# 20x20_adapter_v2.net
KiCad netlist of a schematic drawn in EAGLE
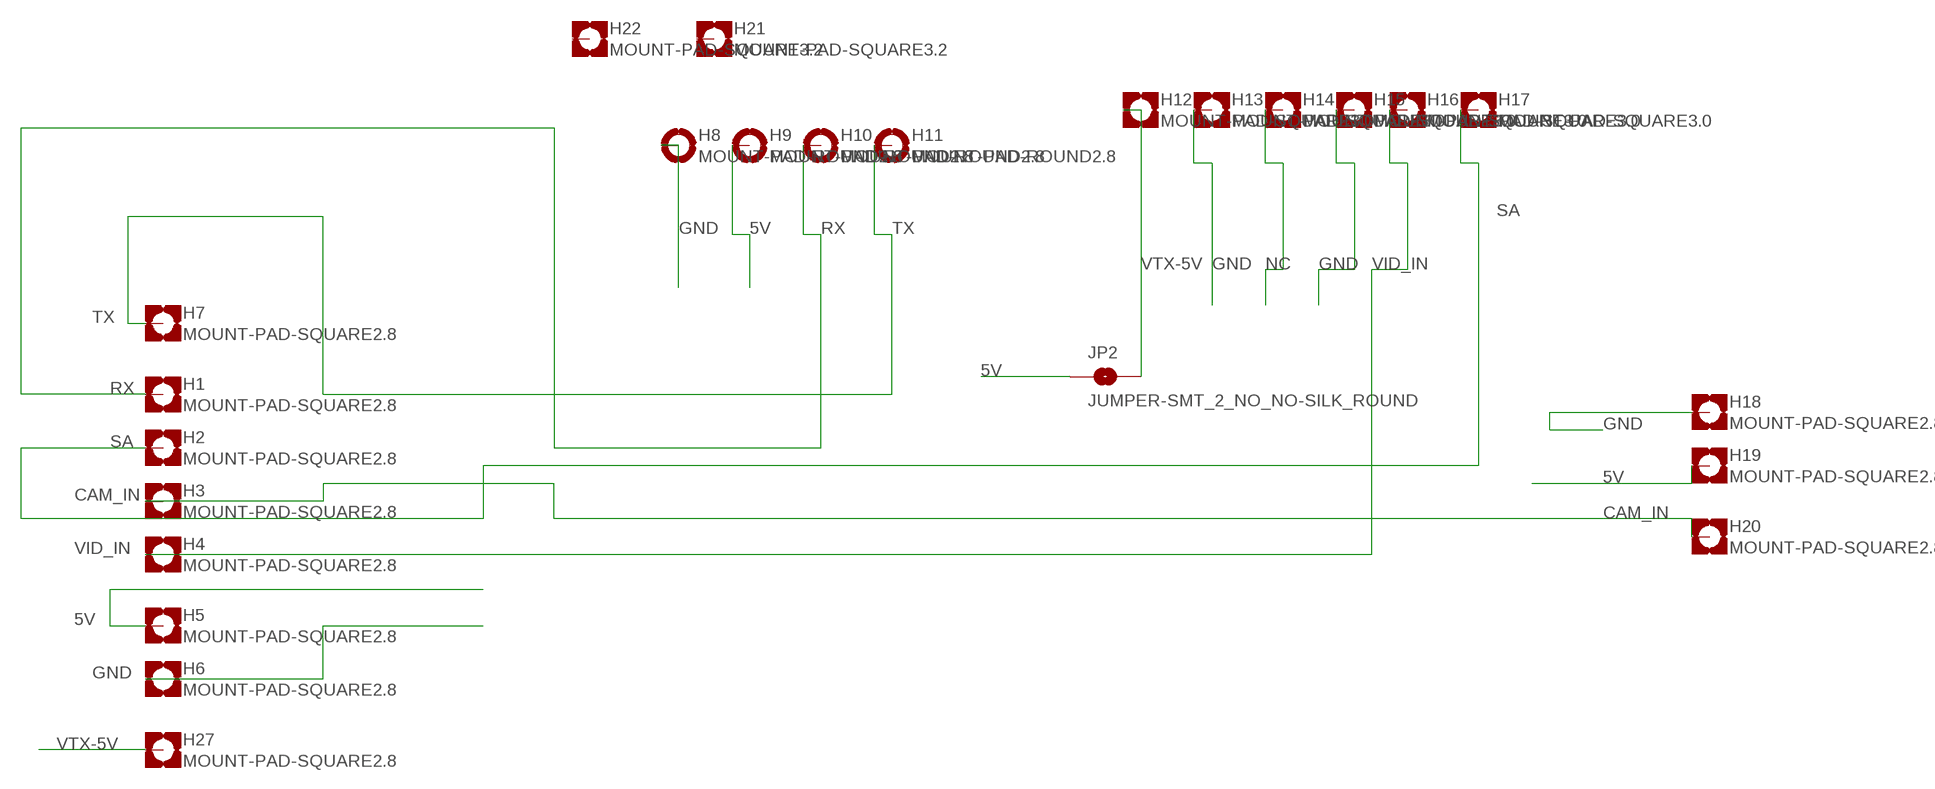
[diagram p0: schematic, sheet 1]

(export (version "E")
  (design (tool "Eeschema 10.0.6"))
  (components
    (comp (ref "H1")
      (value "MOUNT-PAD-SQUARE2.8")
      (footprint "eagle-import:2,8-PAD-SQUARE")
      (libsource (lib "eagle-import") (part "MOUNT-PAD-SQUARE2.8"))
    )
    (comp (ref "H2")
      (value "MOUNT-PAD-SQUARE2.8")
      (footprint "eagle-import:2,8-PAD-SQUARE")
      (libsource (lib "eagle-import") (part "MOUNT-PAD-SQUARE2.8"))
    )
    (comp (ref "H3")
      (value "MOUNT-PAD-SQUARE2.8")
      (footprint "eagle-import:2,8-PAD-SQUARE")
      (libsource (lib "eagle-import") (part "MOUNT-PAD-SQUARE2.8"))
    )
    (comp (ref "H4")
      (value "MOUNT-PAD-SQUARE2.8")
      (footprint "eagle-import:2,8-PAD-SQUARE")
      (libsource (lib "eagle-import") (part "MOUNT-PAD-SQUARE2.8"))
    )
    (comp (ref "H5")
      (value "MOUNT-PAD-SQUARE2.8")
      (footprint "eagle-import:2,8-PAD-SQUARE")
      (libsource (lib "eagle-import") (part "MOUNT-PAD-SQUARE2.8"))
    )
    (comp (ref "H6")
      (value "MOUNT-PAD-SQUARE2.8")
      (footprint "eagle-import:2,8-PAD-SQUARE")
      (libsource (lib "eagle-import") (part "MOUNT-PAD-SQUARE2.8"))
    )
    (comp (ref "H7")
      (value "MOUNT-PAD-SQUARE2.8")
      (footprint "eagle-import:2,8-PAD-SQUARE")
      (libsource (lib "eagle-import") (part "MOUNT-PAD-SQUARE2.8"))
    )
    (comp (ref "H8")
      (value "MOUNT-PAD-ROUND2.8")
      (footprint "eagle-import:1,0-PAD")
      (libsource (lib "eagle-import") (part "MOUNT-PAD-ROUND2.8"))
    )
    (comp (ref "H9")
      (value "MOUNT-PAD-ROUND2.8")
      (footprint "eagle-import:1,0-PAD")
      (libsource (lib "eagle-import") (part "MOUNT-PAD-ROUND2.8"))
    )
    (comp (ref "H10")
      (value "MOUNT-PAD-ROUND2.8")
      (footprint "eagle-import:1,0-PAD")
      (libsource (lib "eagle-import") (part "MOUNT-PAD-ROUND2.8"))
    )
    (comp (ref "H11")
      (value "MOUNT-PAD-ROUND2.8")
      (footprint "eagle-import:1,0-PAD")
      (libsource (lib "eagle-import") (part "MOUNT-PAD-ROUND2.8"))
    )
    (comp (ref "H12")
      (value "MOUNT-PAD-SQUARE3.0")
      (footprint "eagle-import:1,5-PAD-SQUARE")
      (libsource (lib "eagle-import") (part "MOUNT-PAD-SQUARE3.0"))
    )
    (comp (ref "H13")
      (value "MOUNT-PAD-SQUARE3.0")
      (footprint "eagle-import:1,5-PAD-SQUARE")
      (libsource (lib "eagle-import") (part "MOUNT-PAD-SQUARE3.0"))
    )
    (comp (ref "H14")
      (value "MOUNT-PAD-SQUARE3.0")
      (footprint "eagle-import:1,5-PAD-SQUARE")
      (libsource (lib "eagle-import") (part "MOUNT-PAD-SQUARE3.0"))
    )
    (comp (ref "H15")
      (value "MOUNT-PAD-SQUARE3.0")
      (footprint "eagle-import:1,5-PAD-SQUARE")
      (libsource (lib "eagle-import") (part "MOUNT-PAD-SQUARE3.0"))
    )
    (comp (ref "H16")
      (value "MOUNT-PAD-SQUARE3.0")
      (footprint "eagle-import:1,5-PAD-SQUARE")
      (libsource (lib "eagle-import") (part "MOUNT-PAD-SQUARE3.0"))
    )
    (comp (ref "H17")
      (value "MOUNT-PAD-SQUARE3.0")
      (footprint "eagle-import:1,5-PAD-SQUARE")
      (libsource (lib "eagle-import") (part "MOUNT-PAD-SQUARE3.0"))
    )
    (comp (ref "H18")
      (value "MOUNT-PAD-SQUARE2.8")
      (footprint "eagle-import:2,8-PAD-SQUARE")
      (libsource (lib "eagle-import") (part "MOUNT-PAD-SQUARE2.8"))
    )
    (comp (ref "H19")
      (value "MOUNT-PAD-SQUARE2.8")
      (footprint "eagle-import:2,8-PAD-SQUARE")
      (libsource (lib "eagle-import") (part "MOUNT-PAD-SQUARE2.8"))
    )
    (comp (ref "H20")
      (value "MOUNT-PAD-SQUARE2.8")
      (footprint "eagle-import:2,8-PAD-SQUARE")
      (libsource (lib "eagle-import") (part "MOUNT-PAD-SQUARE2.8"))
    )
    (comp (ref "H21")
      (value "MOUNT-PAD-SQUARE3.2")
      (footprint "eagle-import:3,2-PAD-SQUARE")
      (libsource (lib "eagle-import") (part "MOUNT-PAD-SQUARE3.2"))
    )
    (comp (ref "H22")
      (value "MOUNT-PAD-SQUARE3.2")
      (footprint "eagle-import:3,2-PAD-SQUARE")
      (libsource (lib "eagle-import") (part "MOUNT-PAD-SQUARE3.2"))
    )
    (comp (ref "H27")
      (value "MOUNT-PAD-SQUARE2.8")
      (footprint "eagle-import:2,8-PAD-SQUARE")
      (libsource (lib "eagle-import") (part "MOUNT-PAD-SQUARE2.8"))
    )
    (comp (ref "JP2")
      (value "JUMPER-SMT_2_NO_NO-SILK_ROUND")
      (footprint "eagle-import:SMT-JUMPER_2_NO_NO-SILK_ROUND")
      (libsource (lib "eagle-import") (part "JUMPER-SMT_2_NO_NO-SILK_ROUND"))
    )
  )
  (nets
    (net (code "1") (name "/5V") (class "Default")
      (node (ref "H19") (pin "P$2") (pinfunction "MOUNT_P$2") (pintype "passive"))
      (node (ref "H5") (pin "P$2") (pinfunction "MOUNT_P$2") (pintype "passive"))
      (node (ref "H9") (pin "B1,0") (pinfunction "MOUNT_B1,0") (pintype "passive"))
      (node (ref "JP2") (pin "1") (pinfunction "1_1") (pintype "passive"))
    )
    (net (code "2") (name "/CAM_IN") (class "Default")
      (node (ref "H20") (pin "P$2") (pinfunction "MOUNT_P$2") (pintype "passive"))
      (node (ref "H3") (pin "P$2") (pinfunction "MOUNT_P$2") (pintype "passive"))
    )
    (net (code "3") (name "/GND") (class "Default")
      (node (ref "H13") (pin "P$1") (pinfunction "MOUNT_P$1") (pintype "passive"))
      (node (ref "H15") (pin "P$1") (pinfunction "MOUNT_P$1") (pintype "passive"))
      (node (ref "H18") (pin "P$2") (pinfunction "MOUNT_P$2") (pintype "passive"))
      (node (ref "H6") (pin "P$2") (pinfunction "MOUNT_P$2") (pintype "passive"))
      (node (ref "H8") (pin "B1,0") (pinfunction "MOUNT_B1,0") (pintype "passive"))
    )
    (net (code "4") (name "/NC") (class "Default")
      (node (ref "H14") (pin "P$1") (pinfunction "MOUNT_P$1") (pintype "passive"))
    )
    (net (code "5") (name "/RX") (class "Default")
      (node (ref "H1") (pin "P$2") (pinfunction "MOUNT_P$2") (pintype "passive"))
      (node (ref "H10") (pin "B1,0") (pinfunction "MOUNT_B1,0") (pintype "passive"))
    )
    (net (code "6") (name "/SA") (class "Default")
      (node (ref "H17") (pin "P$1") (pinfunction "MOUNT_P$1") (pintype "passive"))
      (node (ref "H2") (pin "P$2") (pinfunction "MOUNT_P$2") (pintype "passive"))
    )
    (net (code "7") (name "/TX") (class "Default")
      (node (ref "H11") (pin "B1,0") (pinfunction "MOUNT_B1,0") (pintype "passive"))
      (node (ref "H7") (pin "P$2") (pinfunction "MOUNT_P$2") (pintype "passive"))
    )
    (net (code "8") (name "/VID_IN") (class "Default")
      (node (ref "H16") (pin "P$1") (pinfunction "MOUNT_P$1") (pintype "passive"))
      (node (ref "H4") (pin "P$2") (pinfunction "MOUNT_P$2") (pintype "passive"))
    )
    (net (code "9") (name "/VTX-5V") (class "Default")
      (node (ref "H12") (pin "P$1") (pinfunction "MOUNT_P$1") (pintype "passive"))
      (node (ref "H27") (pin "P$2") (pinfunction "MOUNT_P$2") (pintype "passive"))
      (node (ref "JP2") (pin "2") (pinfunction "2_2") (pintype "passive"))
    )
    (net (code "10") (name "unconnected-(H21-MOUNT-PadP$1)") (class "Default")
      (node (ref "H21") (pin "P$1") (pinfunction "MOUNT_P$1") (pintype "passive"))
    )
    (net (code "11") (name "unconnected-(H22-MOUNT-PadP$1)") (class "Default")
      (node (ref "H22") (pin "P$1") (pinfunction "MOUNT_P$1") (pintype "passive"))
    )
  )
)
